# HighVoltageSensor.net
KiCad netlist of a schematic drawn in Altium Designer
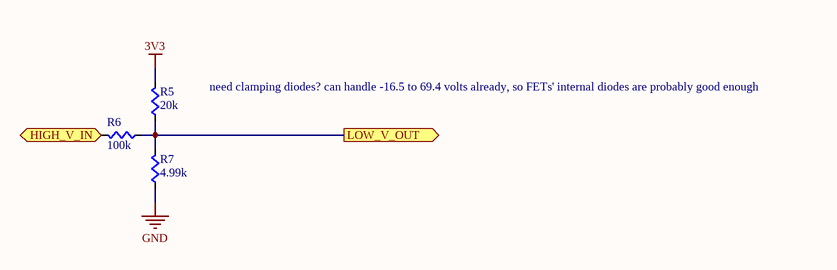
[diagram p0: HighVoltageSensor.SchDoc]

(export (version "E")
  (design (tool "Eeschema 10.0.6"))
  (components
    (comp (ref "R5")
      (value "20k")
      (footprint "RES0603")
      (fields (field (name "Comment") "Res"))
      (libsource (lib "Passives") (part "Res"))
    )
    (comp (ref "R6")
      (value "100k")
      (footprint "RES0603")
      (fields (field (name "Comment") "Res"))
      (libsource (lib "Passives") (part "Res"))
    )
    (comp (ref "R7")
      (value "4.99k")
      (footprint "RES0603")
      (fields (field (name "Comment") "Res"))
      (libsource (lib "Passives") (part "Res"))
    )
  )
  (nets
    (net (code "1") (name "/HIGH_V_IN") (class "Default")
      (node (ref "R6") (pin "1") (pinfunction "A_1") (pintype "passive"))
    )
    (net (code "2") (name "/LOW_V_OUT") (class "Default")
      (node (ref "R5") (pin "2") (pinfunction "B_2") (pintype "passive"))
      (node (ref "R6") (pin "2") (pinfunction "B_2") (pintype "passive"))
      (node (ref "R7") (pin "1") (pinfunction "A_1") (pintype "passive"))
    )
    (net (code "3") (name "3V3") (class "Default")
      (node (ref "R5") (pin "1") (pinfunction "A_1") (pintype "passive"))
    )
    (net (code "4") (name "GND") (class "Default")
      (node (ref "R7") (pin "2") (pinfunction "B_2") (pintype "passive"))
    )
  )
)
